# Adapter_SPI.net
KiCad netlist of a schematic drawn in EAGLE
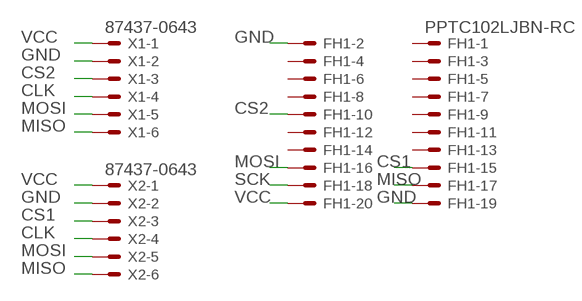
[diagram p0: schematic, sheet 1]

(export (version "E")
  (design (tool "Eeschema 10.0.6"))
  (components
    (comp (ref "FH1")
      (value "PPTC102LJBN-RC")
      (footprint "eagle-import:S5524-ND")
      (libsource (lib "eagle-import") (part "PPTC102LJBN-RC"))
    )
    (comp (ref "X1")
      (value "87437-0643")
      (footprint "eagle-import:87437-06")
      (fields (field (name "MF") "MOLEX"))
      (libsource (lib "eagle-import") (part "8743?-06374"))
    )
    (comp (ref "X2")
      (value "87437-0643")
      (footprint "eagle-import:87437-06")
      (fields (field (name "MF") "MOLEX"))
      (libsource (lib "eagle-import") (part "8743?-06374"))
    )
  )
  (nets
    (net (code "1") (name "/CLK") (class "Default")
      (node (ref "X1") (pin "4") (pinfunction "S_4") (pintype "passive"))
      (node (ref "X2") (pin "4") (pinfunction "S_4") (pintype "passive"))
    )
    (net (code "2") (name "/CS1") (class "Default")
      (node (ref "FH1") (pin "P$15") (pinfunction "S_P$15") (pintype "passive"))
      (node (ref "X2") (pin "3") (pinfunction "S_3") (pintype "passive"))
    )
    (net (code "3") (name "/CS2") (class "Default")
      (node (ref "FH1") (pin "P$10") (pinfunction "S_P$10") (pintype "passive"))
      (node (ref "X1") (pin "3") (pinfunction "S_3") (pintype "passive"))
    )
    (net (code "4") (name "/GND") (class "Default")
      (node (ref "FH1") (pin "P$19") (pinfunction "S_P$19") (pintype "passive"))
      (node (ref "FH1") (pin "P$2") (pinfunction "S_P$2") (pintype "passive"))
      (node (ref "X1") (pin "2") (pinfunction "S_2") (pintype "passive"))
      (node (ref "X2") (pin "2") (pinfunction "S_2") (pintype "passive"))
    )
    (net (code "5") (name "/MISO") (class "Default")
      (node (ref "FH1") (pin "P$17") (pinfunction "S_P$17") (pintype "passive"))
      (node (ref "X1") (pin "6") (pinfunction "S_6") (pintype "passive"))
      (node (ref "X2") (pin "6") (pinfunction "S_6") (pintype "passive"))
    )
    (net (code "6") (name "/MOSI") (class "Default")
      (node (ref "FH1") (pin "P$16") (pinfunction "S_P$16") (pintype "passive"))
      (node (ref "X1") (pin "5") (pinfunction "S_5") (pintype "passive"))
      (node (ref "X2") (pin "5") (pinfunction "S_5") (pintype "passive"))
    )
    (net (code "7") (name "/SCK") (class "Default")
      (node (ref "FH1") (pin "P$18") (pinfunction "S_P$18") (pintype "passive"))
    )
    (net (code "8") (name "/VCC") (class "Default")
      (node (ref "FH1") (pin "P$20") (pinfunction "S_P$20") (pintype "passive"))
      (node (ref "X1") (pin "1") (pinfunction "S_1") (pintype "passive"))
      (node (ref "X2") (pin "1") (pinfunction "S_1") (pintype "passive"))
    )
    (net (code "9") (name "unconnected-(FH1A-S-PadP$1)") (class "Default")
      (node (ref "FH1") (pin "P$1") (pinfunction "S_P$1") (pintype "passive"))
    )
    (net (code "10") (name "unconnected-(FH1C-S-PadP$11)") (class "Default")
      (node (ref "FH1") (pin "P$11") (pinfunction "S_P$11") (pintype "passive"))
    )
    (net (code "11") (name "unconnected-(FH1D-S-PadP$12)") (class "Default")
      (node (ref "FH1") (pin "P$12") (pinfunction "S_P$12") (pintype "passive"))
    )
    (net (code "12") (name "unconnected-(FH1E-S-PadP$13)") (class "Default")
      (node (ref "FH1") (pin "P$13") (pinfunction "S_P$13") (pintype "passive"))
    )
    (net (code "13") (name "unconnected-(FH1F-S-PadP$14)") (class "Default")
      (node (ref "FH1") (pin "P$14") (pinfunction "S_P$14") (pintype "passive"))
    )
    (net (code "14") (name "unconnected-(FH1N-S-PadP$3)") (class "Default")
      (node (ref "FH1") (pin "P$3") (pinfunction "S_P$3") (pintype "passive"))
    )
    (net (code "15") (name "unconnected-(FH1O-S-PadP$4)") (class "Default")
      (node (ref "FH1") (pin "P$4") (pinfunction "S_P$4") (pintype "passive"))
    )
    (net (code "16") (name "unconnected-(FH1P-S-PadP$5)") (class "Default")
      (node (ref "FH1") (pin "P$5") (pinfunction "S_P$5") (pintype "passive"))
    )
    (net (code "17") (name "unconnected-(FH1Q-S-PadP$6)") (class "Default")
      (node (ref "FH1") (pin "P$6") (pinfunction "S_P$6") (pintype "passive"))
    )
    (net (code "18") (name "unconnected-(FH1R-S-PadP$7)") (class "Default")
      (node (ref "FH1") (pin "P$7") (pinfunction "S_P$7") (pintype "passive"))
    )
    (net (code "19") (name "unconnected-(FH1S-S-PadP$8)") (class "Default")
      (node (ref "FH1") (pin "P$8") (pinfunction "S_P$8") (pintype "passive"))
    )
    (net (code "20") (name "unconnected-(FH1T-S-PadP$9)") (class "Default")
      (node (ref "FH1") (pin "P$9") (pinfunction "S_P$9") (pintype "passive"))
    )
  )
)
